# remote.net
KiCad netlist of a schematic drawn in EAGLE
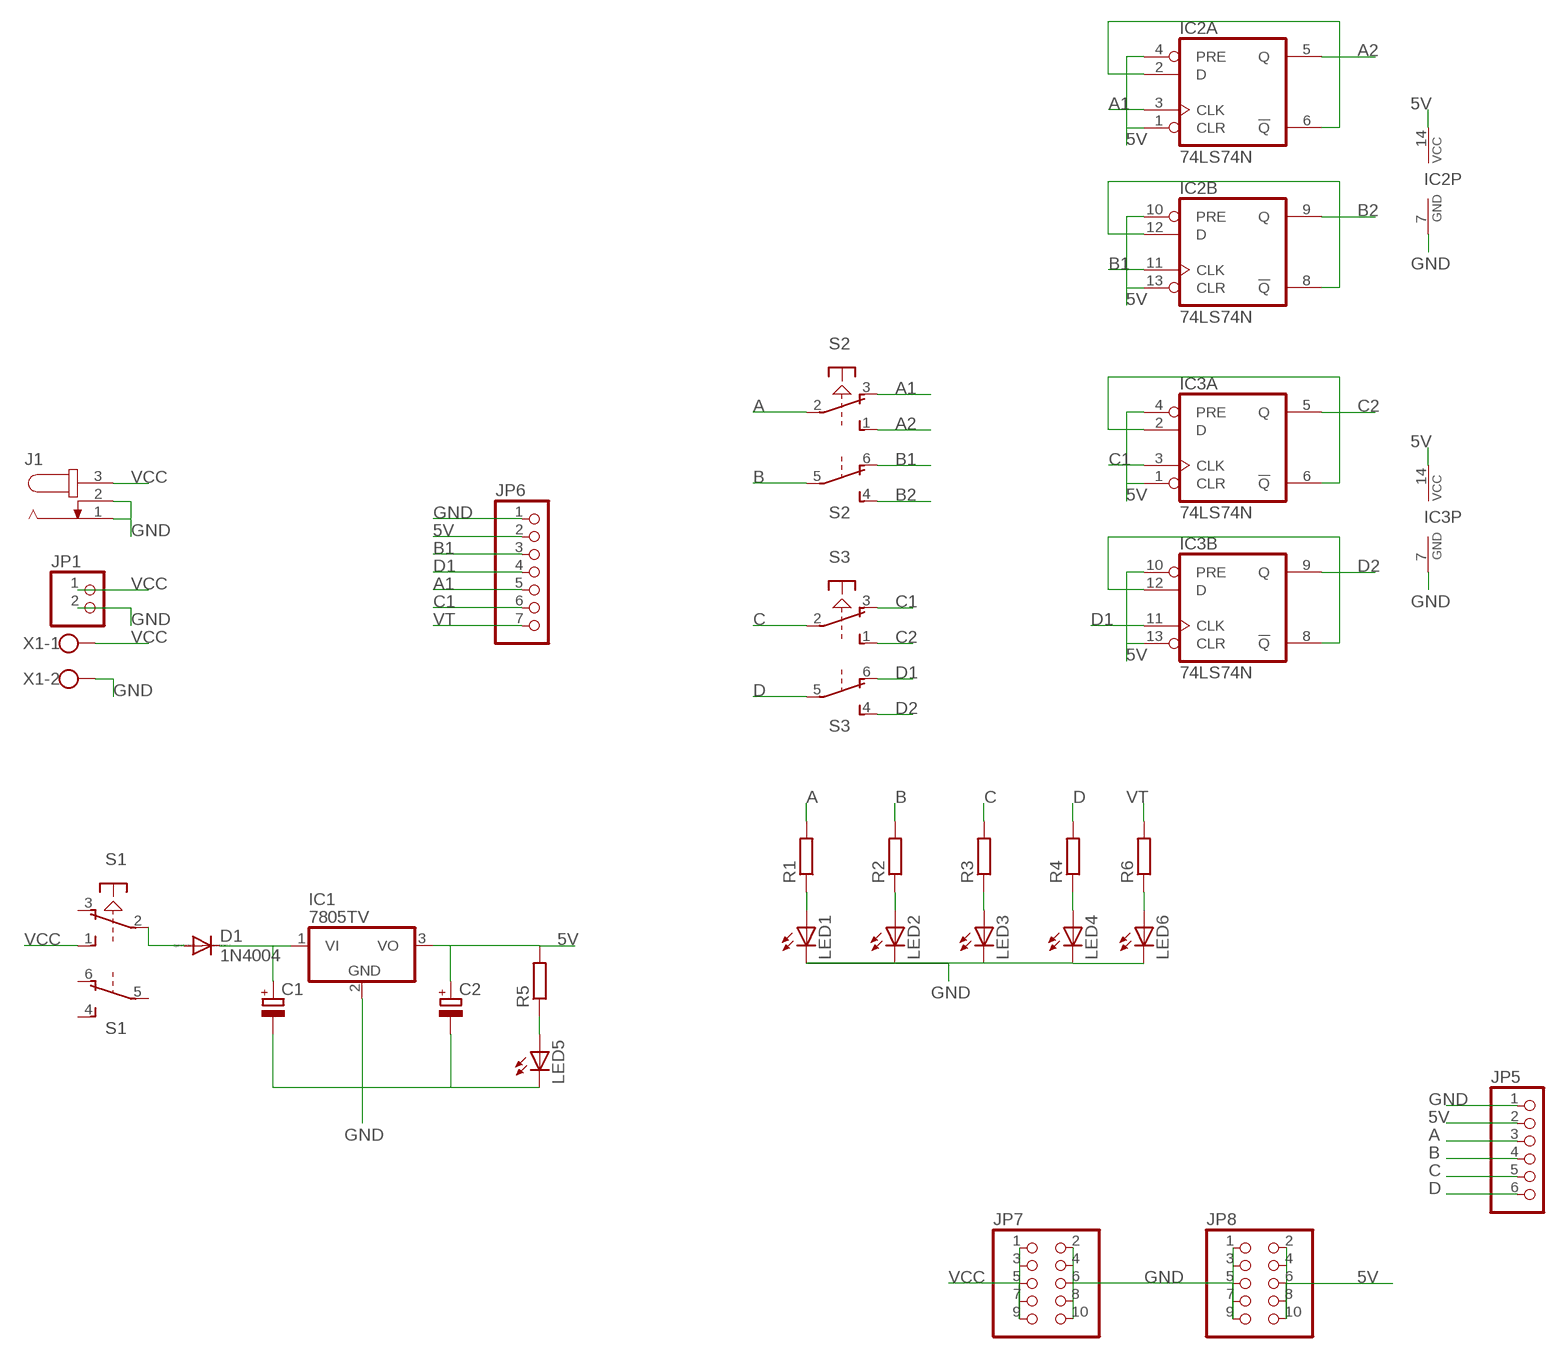
[diagram p0: schematic, sheet 1]

(export (version "E")
  (design (tool "Eeschema 10.0.6"))
  (components
    (comp (ref "C1")
      (value "CPOL-EUE2.5-5")
      (footprint "eagle-import:E2,5-5")
      (libsource (lib "eagle-import") (part "CPOL-EUE2.5-5"))
    )
    (comp (ref "C2")
      (value "CPOL-EUE2.5-5")
      (footprint "eagle-import:E2,5-5")
      (libsource (lib "eagle-import") (part "CPOL-EUE2.5-5"))
    )
    (comp (ref "D1")
      (value "1N4004")
      (footprint "eagle-import:DO41-10")
      (libsource (lib "eagle-import") (part "1N4004"))
    )
    (comp (ref "IC1")
      (value "7805TV")
      (footprint "eagle-import:TO220V")
      (libsource (lib "eagle-import") (part "78TV05"))
    )
    (comp (ref "IC2")
      (value "74LS74N")
      (footprint "eagle-import:DIL14")
      (libsource (lib "eagle-import") (part "7474NLS"))
    )
    (comp (ref "IC3")
      (value "74LS74N")
      (footprint "eagle-import:DIL14")
      (libsource (lib "eagle-import") (part "7474NLS"))
    )
    (comp (ref "J1")
      (value "JACK-PLUG0")
      (footprint "eagle-import:SPC4077")
      (libsource (lib "eagle-import") (part "JACK-PLUG0"))
    )
    (comp (ref "JP1")
      (value "PINHD-1X2")
      (footprint "eagle-import:1X02")
      (libsource (lib "eagle-import") (part "PINHD-1X2"))
    )
    (comp (ref "JP5")
      (value "PINHD-1X6")
      (footprint "eagle-import:1X06")
      (libsource (lib "eagle-import") (part "PINHD-1X6"))
    )
    (comp (ref "JP6")
      (value "PINHD-1X7")
      (footprint "eagle-import:1X07")
      (libsource (lib "eagle-import") (part "PINHD-1X7"))
    )
    (comp (ref "JP7")
      (value "PINHD-2X5")
      (footprint "eagle-import:2X05")
      (libsource (lib "eagle-import") (part "PINHD-2X5"))
    )
    (comp (ref "JP8")
      (value "PINHD-2X5")
      (footprint "eagle-import:2X05")
      (libsource (lib "eagle-import") (part "PINHD-2X5"))
    )
    (comp (ref "LED1")
      (value "LED3MM")
      (footprint "eagle-import:LED3MM")
      (libsource (lib "eagle-import") (part "LED3MM"))
    )
    (comp (ref "LED2")
      (value "LED3MM")
      (footprint "eagle-import:LED3MM")
      (libsource (lib "eagle-import") (part "LED3MM"))
    )
    (comp (ref "LED3")
      (value "LED3MM")
      (footprint "eagle-import:LED3MM")
      (libsource (lib "eagle-import") (part "LED3MM"))
    )
    (comp (ref "LED4")
      (value "LED3MM")
      (footprint "eagle-import:LED3MM")
      (libsource (lib "eagle-import") (part "LED3MM"))
    )
    (comp (ref "LED5")
      (value "LED3MM")
      (footprint "eagle-import:LED3MM")
      (libsource (lib "eagle-import") (part "LED3MM"))
    )
    (comp (ref "LED6")
      (value "LED3MM")
      (footprint "eagle-import:LED3MM")
      (libsource (lib "eagle-import") (part "LED3MM"))
    )
    (comp (ref "R1")
      (value "R-EU_0207/7")
      (footprint "eagle-import:0207_7")
      (libsource (lib "eagle-import") (part "R-EU_0207/7"))
    )
    (comp (ref "R2")
      (value "R-EU_0207/7")
      (footprint "eagle-import:0207_7")
      (libsource (lib "eagle-import") (part "R-EU_0207/7"))
    )
    (comp (ref "R3")
      (value "R-EU_0207/7")
      (footprint "eagle-import:0207_7")
      (libsource (lib "eagle-import") (part "R-EU_0207/7"))
    )
    (comp (ref "R4")
      (value "R-EU_0207/7")
      (footprint "eagle-import:0207_7")
      (libsource (lib "eagle-import") (part "R-EU_0207/7"))
    )
    (comp (ref "R5")
      (value "R-EU_0207/7")
      (footprint "eagle-import:0207_7")
      (libsource (lib "eagle-import") (part "R-EU_0207/7"))
    )
    (comp (ref "R6")
      (value "R-EU_0207/7")
      (footprint "eagle-import:0207_7")
      (libsource (lib "eagle-import") (part "R-EU_0207/7"))
    )
    (comp (ref "S1")
      (value "PVA2R")
      (footprint "eagle-import:PVA2R")
      (libsource (lib "eagle-import") (part "PVA2R"))
    )
    (comp (ref "S2")
      (value "PVA2R")
      (footprint "eagle-import:PVA2R")
      (libsource (lib "eagle-import") (part "PVA2R"))
    )
    (comp (ref "S3")
      (value "PVA2R")
      (footprint "eagle-import:PVA2R")
      (libsource (lib "eagle-import") (part "PVA2R"))
    )
    (comp (ref "X1")
      (value "W237-102")
      (footprint "eagle-import:W237-102")
      (fields (field (name "MPN") "237-102"))
      (libsource (lib "eagle-import") (part "W237-102"))
    )
  )
  (nets
    (net (code "1") (name "/5V") (class "Default")
      (node (ref "C2") (pin "+") (pinfunction "+_+") (pintype "passive"))
      (node (ref "IC1") (pin "3") (pinfunction "VO_3") (pintype "passive"))
      (node (ref "IC2") (pin "1") (pinfunction "CLR_1") (pintype "input"))
      (node (ref "IC2") (pin "10") (pinfunction "PRE_10") (pintype "input"))
      (node (ref "IC2") (pin "13") (pinfunction "CLR_13") (pintype "input"))
      (node (ref "IC2") (pin "14") (pinfunction "VCC_14") (pintype "power_in"))
      (node (ref "IC2") (pin "4") (pinfunction "PRE_4") (pintype "input"))
      (node (ref "IC3") (pin "1") (pinfunction "CLR_1") (pintype "input"))
      (node (ref "IC3") (pin "10") (pinfunction "PRE_10") (pintype "input"))
      (node (ref "IC3") (pin "13") (pinfunction "CLR_13") (pintype "input"))
      (node (ref "IC3") (pin "14") (pinfunction "VCC_14") (pintype "power_in"))
      (node (ref "IC3") (pin "4") (pinfunction "PRE_4") (pintype "input"))
      (node (ref "JP5") (pin "2") (pinfunction "2_2") (pintype "passive"))
      (node (ref "JP6") (pin "2") (pinfunction "2_2") (pintype "passive"))
      (node (ref "JP8") (pin "10") (pinfunction "10_10") (pintype "passive"))
      (node (ref "JP8") (pin "2") (pinfunction "2_2") (pintype "passive"))
      (node (ref "JP8") (pin "4") (pinfunction "4_4") (pintype "passive"))
      (node (ref "JP8") (pin "6") (pinfunction "6_6") (pintype "passive"))
      (node (ref "JP8") (pin "8") (pinfunction "8_8") (pintype "passive"))
      (node (ref "R5") (pin "2") (pinfunction "2_2") (pintype "passive"))
    )
    (net (code "2") (name "/A") (class "Default")
      (node (ref "JP5") (pin "3") (pinfunction "3_3") (pintype "passive"))
      (node (ref "R1") (pin "2") (pinfunction "2_2") (pintype "passive"))
      (node (ref "S2") (pin "2") (pinfunction "P_2") (pintype "passive"))
    )
    (net (code "3") (name "/A1") (class "Default")
      (node (ref "IC2") (pin "3") (pinfunction "CLK_3") (pintype "input"))
      (node (ref "JP6") (pin "5") (pinfunction "5_5") (pintype "passive"))
      (node (ref "S2") (pin "3") (pinfunction "O_3") (pintype "passive"))
    )
    (net (code "4") (name "/A2") (class "Default")
      (node (ref "IC2") (pin "5") (pinfunction "Q_5") (pintype "output"))
      (node (ref "S2") (pin "1") (pinfunction "S_1") (pintype "passive"))
    )
    (net (code "5") (name "/B") (class "Default")
      (node (ref "JP5") (pin "4") (pinfunction "4_4") (pintype "passive"))
      (node (ref "R2") (pin "2") (pinfunction "2_2") (pintype "passive"))
      (node (ref "S2") (pin "5") (pinfunction "P_5") (pintype "passive"))
    )
    (net (code "6") (name "/B1") (class "Default")
      (node (ref "IC2") (pin "11") (pinfunction "CLK_11") (pintype "input"))
      (node (ref "JP6") (pin "3") (pinfunction "3_3") (pintype "passive"))
      (node (ref "S2") (pin "6") (pinfunction "O_6") (pintype "passive"))
    )
    (net (code "7") (name "/B2") (class "Default")
      (node (ref "IC2") (pin "9") (pinfunction "Q_9") (pintype "output"))
      (node (ref "S2") (pin "4") (pinfunction "S_4") (pintype "passive"))
    )
    (net (code "8") (name "/C") (class "Default")
      (node (ref "JP5") (pin "5") (pinfunction "5_5") (pintype "passive"))
      (node (ref "R3") (pin "2") (pinfunction "2_2") (pintype "passive"))
      (node (ref "S3") (pin "2") (pinfunction "P_2") (pintype "passive"))
    )
    (net (code "9") (name "/C1") (class "Default")
      (node (ref "IC3") (pin "3") (pinfunction "CLK_3") (pintype "input"))
      (node (ref "JP6") (pin "6") (pinfunction "6_6") (pintype "passive"))
      (node (ref "S3") (pin "3") (pinfunction "O_3") (pintype "passive"))
    )
    (net (code "10") (name "/C2") (class "Default")
      (node (ref "IC3") (pin "5") (pinfunction "Q_5") (pintype "output"))
      (node (ref "S3") (pin "1") (pinfunction "S_1") (pintype "passive"))
    )
    (net (code "11") (name "/D") (class "Default")
      (node (ref "JP5") (pin "6") (pinfunction "6_6") (pintype "passive"))
      (node (ref "R4") (pin "2") (pinfunction "2_2") (pintype "passive"))
      (node (ref "S3") (pin "5") (pinfunction "P_5") (pintype "passive"))
    )
    (net (code "12") (name "/D1") (class "Default")
      (node (ref "IC3") (pin "11") (pinfunction "CLK_11") (pintype "input"))
      (node (ref "JP6") (pin "4") (pinfunction "4_4") (pintype "passive"))
      (node (ref "S3") (pin "6") (pinfunction "O_6") (pintype "passive"))
    )
    (net (code "13") (name "/D2") (class "Default")
      (node (ref "IC3") (pin "9") (pinfunction "Q_9") (pintype "output"))
      (node (ref "S3") (pin "4") (pinfunction "S_4") (pintype "passive"))
    )
    (net (code "14") (name "/GND") (class "Default")
      (node (ref "C1") (pin "-") (pinfunction "-_-") (pintype "passive"))
      (node (ref "C2") (pin "-") (pinfunction "-_-") (pintype "passive"))
      (node (ref "IC1") (pin "2") (pinfunction "GND_2") (pintype "passive"))
      (node (ref "IC2") (pin "7") (pinfunction "GND_7") (pintype "power_in"))
      (node (ref "IC3") (pin "7") (pinfunction "GND_7") (pintype "power_in"))
      (node (ref "J1") (pin "1") (pinfunction "1_1") (pintype "passive"))
      (node (ref "J1") (pin "2") (pinfunction "2_2") (pintype "passive"))
      (node (ref "JP1") (pin "2") (pinfunction "2_2") (pintype "passive"))
      (node (ref "JP5") (pin "1") (pinfunction "1_1") (pintype "passive"))
      (node (ref "JP6") (pin "1") (pinfunction "1_1") (pintype "passive"))
      (node (ref "JP7") (pin "10") (pinfunction "10_10") (pintype "passive"))
      (node (ref "JP7") (pin "2") (pinfunction "2_2") (pintype "passive"))
      (node (ref "JP7") (pin "4") (pinfunction "4_4") (pintype "passive"))
      (node (ref "JP7") (pin "6") (pinfunction "6_6") (pintype "passive"))
      (node (ref "JP7") (pin "8") (pinfunction "8_8") (pintype "passive"))
      (node (ref "JP8") (pin "1") (pinfunction "1_1") (pintype "passive"))
      (node (ref "JP8") (pin "3") (pinfunction "3_3") (pintype "passive"))
      (node (ref "JP8") (pin "5") (pinfunction "5_5") (pintype "passive"))
      (node (ref "JP8") (pin "7") (pinfunction "7_7") (pintype "passive"))
      (node (ref "JP8") (pin "9") (pinfunction "9_9") (pintype "passive"))
      (node (ref "LED1") (pin "K") (pinfunction "C_K") (pintype "passive"))
      (node (ref "LED2") (pin "K") (pinfunction "C_K") (pintype "passive"))
      (node (ref "LED3") (pin "K") (pinfunction "C_K") (pintype "passive"))
      (node (ref "LED4") (pin "K") (pinfunction "C_K") (pintype "passive"))
      (node (ref "LED5") (pin "K") (pinfunction "C_K") (pintype "passive"))
      (node (ref "LED6") (pin "K") (pinfunction "C_K") (pintype "passive"))
      (node (ref "X1") (pin "2") (pinfunction "KL_2") (pintype "passive"))
    )
    (net (code "15") (name "/VCC") (class "Default")
      (node (ref "J1") (pin "3") (pinfunction "3_3") (pintype "passive"))
      (node (ref "JP1") (pin "1") (pinfunction "1_1") (pintype "passive"))
      (node (ref "JP7") (pin "1") (pinfunction "1_1") (pintype "passive"))
      (node (ref "JP7") (pin "3") (pinfunction "3_3") (pintype "passive"))
      (node (ref "JP7") (pin "5") (pinfunction "5_5") (pintype "passive"))
      (node (ref "JP7") (pin "7") (pinfunction "7_7") (pintype "passive"))
      (node (ref "JP7") (pin "9") (pinfunction "9_9") (pintype "passive"))
      (node (ref "S1") (pin "1") (pinfunction "S_1") (pintype "passive"))
      (node (ref "X1") (pin "1") (pinfunction "KL_1") (pintype "passive"))
    )
    (net (code "16") (name "/VT") (class "Default")
      (node (ref "JP6") (pin "7") (pinfunction "7_7") (pintype "passive"))
      (node (ref "R6") (pin "2") (pinfunction "2_2") (pintype "passive"))
    )
    (net (code "17") (name "Net-(IC1-VI)") (class "Default")
      (node (ref "C1") (pin "+") (pinfunction "+_+") (pintype "passive"))
      (node (ref "D1") (pin "C") (pinfunction "C_C") (pintype "passive"))
      (node (ref "IC1") (pin "1") (pinfunction "VI_1") (pintype "input"))
    )
    (net (code "18") (name "Net-(IC2A-D)") (class "Default")
      (node (ref "IC2") (pin "2") (pinfunction "D_2") (pintype "input"))
      (node (ref "IC2") (pin "6") (pinfunction "~{Q}_6") (pintype "output"))
    )
    (net (code "19") (name "Net-(IC2B-D)") (class "Default")
      (node (ref "IC2") (pin "12") (pinfunction "D_12") (pintype "input"))
      (node (ref "IC2") (pin "8") (pinfunction "~{Q}_8") (pintype "output"))
    )
    (net (code "20") (name "Net-(IC3A-D)") (class "Default")
      (node (ref "IC3") (pin "2") (pinfunction "D_2") (pintype "input"))
      (node (ref "IC3") (pin "6") (pinfunction "~{Q}_6") (pintype "output"))
    )
    (net (code "21") (name "Net-(IC3B-D)") (class "Default")
      (node (ref "IC3") (pin "12") (pinfunction "D_12") (pintype "input"))
      (node (ref "IC3") (pin "8") (pinfunction "~{Q}_8") (pintype "output"))
    )
    (net (code "22") (name "Net-(LED1-PadA)") (class "Default")
      (node (ref "LED1") (pin "A") (pinfunction "A_A") (pintype "passive"))
      (node (ref "R1") (pin "1") (pinfunction "1_1") (pintype "passive"))
    )
    (net (code "23") (name "Net-(LED2-PadA)") (class "Default")
      (node (ref "LED2") (pin "A") (pinfunction "A_A") (pintype "passive"))
      (node (ref "R2") (pin "1") (pinfunction "1_1") (pintype "passive"))
    )
    (net (code "24") (name "Net-(LED3-PadA)") (class "Default")
      (node (ref "LED3") (pin "A") (pinfunction "A_A") (pintype "passive"))
      (node (ref "R3") (pin "1") (pinfunction "1_1") (pintype "passive"))
    )
    (net (code "25") (name "Net-(LED4-PadA)") (class "Default")
      (node (ref "LED4") (pin "A") (pinfunction "A_A") (pintype "passive"))
      (node (ref "R4") (pin "1") (pinfunction "1_1") (pintype "passive"))
    )
    (net (code "26") (name "Net-(LED5-PadA)") (class "Default")
      (node (ref "LED5") (pin "A") (pinfunction "A_A") (pintype "passive"))
      (node (ref "R5") (pin "1") (pinfunction "1_1") (pintype "passive"))
    )
    (net (code "27") (name "Net-(LED6-PadA)") (class "Default")
      (node (ref "LED6") (pin "A") (pinfunction "A_A") (pintype "passive"))
      (node (ref "R6") (pin "1") (pinfunction "1_1") (pintype "passive"))
    )
    (net (code "28") (name "Net-(S1A-P)") (class "Default")
      (node (ref "D1") (pin "A") (pinfunction "A_A") (pintype "passive"))
      (node (ref "S1") (pin "2") (pinfunction "P_2") (pintype "passive"))
    )
    (net (code "29") (name "unconnected-(S1A-O-Pad3)") (class "Default")
      (node (ref "S1") (pin "3") (pinfunction "O_3") (pintype "passive"))
    )
    (net (code "30") (name "unconnected-(S1B-O-Pad6)") (class "Default")
      (node (ref "S1") (pin "6") (pinfunction "O_6") (pintype "passive"))
    )
    (net (code "31") (name "unconnected-(S1B-P-Pad5)") (class "Default")
      (node (ref "S1") (pin "5") (pinfunction "P_5") (pintype "passive"))
    )
    (net (code "32") (name "unconnected-(S1B-S-Pad4)") (class "Default")
      (node (ref "S1") (pin "4") (pinfunction "S_4") (pintype "passive"))
    )
  )
)
